# Power_Input.net
KiCad netlist of a schematic drawn in Altium Designer
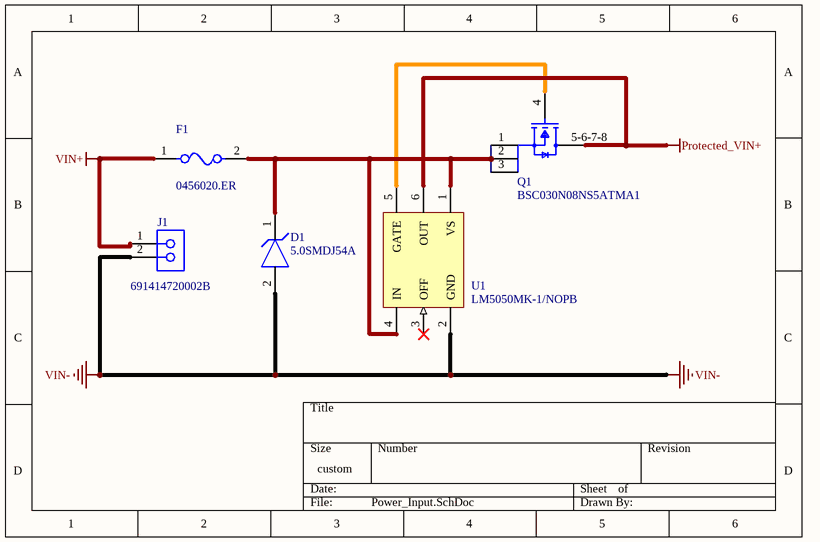
[diagram p0: Power_Input.SchDoc]

(export (version "E")
  (design (tool "Eeschema 10.0.6"))
  (components
    (comp (ref "D1")
      (value "5.0SMDJ54A")
      (footprint "FP-5_0SMDJ-MFG")
      (description "TVS DIODE 54V 87.1V DO214AB")
      (libsource (lib "Altium Content Vault") (part "673ecd2ea4d7fb87b4005b0cb348b7d"))
    )
    (comp (ref "F1")
      (value "0456020.ER")
      (footprint "FP-0456-MFG")
      (description "FUSE BOARD MNT 20A 125VAC 100VDC")
      (fields
        (field (name "MANUFACTURER") "Littelfuse Inc")
        (field (name "OCTOPART") "https://octopart.com/0456020.er-littelfuse-7502596")
      )
      (libsource (lib "Altium Content Vault") (part "5bcf9b9f640e542cf0359d10258e979"))
    )
    (comp (ref "J1")
      (value "691414720002B")
      (footprint "691414720002B")
      (description "Terminal Block, Wtb, 2Way, 28-14Awg Rohs Compliant: Yes")
      (fields (field (name "VOLTAGE") "300V"))
      (libsource (lib "Altium Content Vault") (part "TBL - 1R - 02P - Female"))
    )
    (comp (ref "Q1")
      (value "BSC030N08NS5ATMA1")
      (footprint "FP-PG-TDSON-8-MFG")
      (description "MOSFET N-CH 80V 100A 8TDSON")
      (fields
        (field (name "MANUFACTURER") "Infineon")
        (field (name "OCTOPART") "https://octopart.com/bsc030n08ns5atma1-infineon-52825708")
      )
      (libsource (lib "Altium Content Vault") (part "95ca5d46c4c8fe7d84c4fb5e2abfe3c"))
    )
    (comp (ref "U1")
      (value "LM5050MK-1/NOPB")
      (footprint "DDC0006A_N")
      (description "High Side OR-ing FET Controller, 6-pin TSOT, 1000 Reel")
      (fields (field (name "MANUFACTURER") "Texas Instruments"))
      (libsource (lib "Altium Content Vault") (part "PM-SMPS-LM5050-IL6"))
    )
  )
  (nets
    (net (code "1") (name "Net-(D1-C)") (class "Default")
      (node (ref "D1") (pin "1") (pinfunction "C_1") (pintype "passive"))
      (node (ref "F1") (pin "2") (pinfunction "2_2") (pintype "passive"))
      (node (ref "Q1") (pin "1") (pinfunction "S_1") (pintype "passive"))
      (node (ref "Q1") (pin "2") (pinfunction "S_2") (pintype "passive"))
      (node (ref "Q1") (pin "3") (pinfunction "S_3") (pintype "passive"))
      (node (ref "U1") (pin "1") (pinfunction "VS_1") (pintype "power_in"))
      (node (ref "U1") (pin "4") (pinfunction "IN_4") (pintype "power_in"))
    )
    (net (code "2") (name "Net-(Q1-G)") (class "Default")
      (node (ref "Q1") (pin "4") (pinfunction "G_4") (pintype "passive"))
      (node (ref "U1") (pin "5") (pinfunction "GATE_5") (pintype "power_in"))
    )
    (net (code "3") (name "Protected_VIN+") (class "Default")
      (node (ref "Q1") (pin "5-6-7-8") (pinfunction "D_5-6-7-8") (pintype "passive"))
      (node (ref "U1") (pin "6") (pinfunction "OUT_6") (pintype "power_in"))
    )
    (net (code "4") (name "VIN+") (class "Default")
      (node (ref "F1") (pin "1") (pinfunction "1_1") (pintype "passive"))
      (node (ref "J1") (pin "1") (pinfunction "1_1") (pintype "passive"))
    )
    (net (code "5") (name "VIN-") (class "Default")
      (node (ref "D1") (pin "2") (pinfunction "A_2") (pintype "passive"))
      (node (ref "J1") (pin "2") (pinfunction "2_2") (pintype "passive"))
      (node (ref "U1") (pin "2") (pinfunction "GND_2") (pintype "power_in"))
    )
    (net (code "6") (name "unconnected-(U1-OFF-Pad3)") (class "Default")
      (node (ref "U1") (pin "3") (pinfunction "OFF_3") (pintype "input+no_connect"))
    )
  )
)
